# alimentacion.net
KiCad netlist of a schematic drawn in Altium Designer
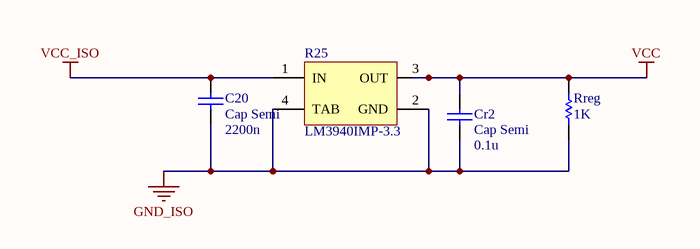
[diagram p0: alimentacion.SchDoc]

(export (version "E")
  (design (tool "Eeschema 10.0.6"))
  (components
    (comp (ref "C20")
      (value "Cap Semi")
      (footprint "C1206")
      (description "Capacitor (Semiconductor SIM Model)")
      (fields (field (name "ALTIUM_VALUE") "2200n") (field (name "PUBLISHER") "Altium Limited"))
      (libsource (lib "Miscellaneous Devices") (part "Cap Semi"))
    )
    (comp (ref "Cr2")
      (value "Cap Semi")
      (footprint "1608[0603]")
      (description "Capacitor (Semiconductor SIM Model)")
      (fields (field (name "ALTIUM_VALUE") "0.1u") (field (name "PUBLISHER") "Altium Limited"))
      (libsource (lib "Miscellaneous Devices") (part "Cap Semi"))
    )
    (comp (ref "R25")
      (value "LM3940IMP-3.3")
      (footprint "MP04A_N")
      (description "1A Low Dropout Regulator for 5V to 3.3V Conversion, 4-pin SOT-223")
      (fields
        (field (name "MANUFACTURER") "National Semiconductor")
        (field (name "PUBLISHER") "Altium Limited")
      )
      (libsource (lib "NSC LDO") (part "LM3940IMP-3.3"))
    )
    (comp (ref "Rreg")
      (value "1K")
      (footprint "2012[0805]")
      (description "Semiconductor Resistor")
      (fields (field (name "Comment") "Res Semi") (field (name "PUBLISHER") "Altium Limited"))
      (libsource (lib "Miscellaneous Devices") (part "Res Semi"))
    )
  )
  (nets
    (net (code "1") (name "GND_ISO") (class "Default")
      (node (ref "C20") (pin "1") (pinfunction "1_1") (pintype "passive"))
      (node (ref "Cr2") (pin "1") (pinfunction "1_1") (pintype "passive"))
      (node (ref "R25") (pin "2") (pinfunction "GND_2") (pintype "power_in"))
      (node (ref "R25") (pin "4") (pinfunction "TAB_4") (pintype "power_in"))
      (node (ref "Rreg") (pin "1") (pinfunction "1_1") (pintype "passive"))
    )
    (net (code "2") (name "VCC") (class "Default")
      (node (ref "Cr2") (pin "2") (pinfunction "2_2") (pintype "passive"))
      (node (ref "R25") (pin "3") (pinfunction "OUT_3") (pintype "power_in"))
      (node (ref "Rreg") (pin "2") (pinfunction "2_2") (pintype "passive"))
    )
    (net (code "3") (name "VCC_ISO") (class "Default")
      (node (ref "C20") (pin "2") (pinfunction "2_2") (pintype "passive"))
      (node (ref "R25") (pin "1") (pinfunction "IN_1") (pintype "power_in"))
    )
  )
)
